# P04_McuConfig.net
KiCad netlist of a schematic drawn in Altium Designer
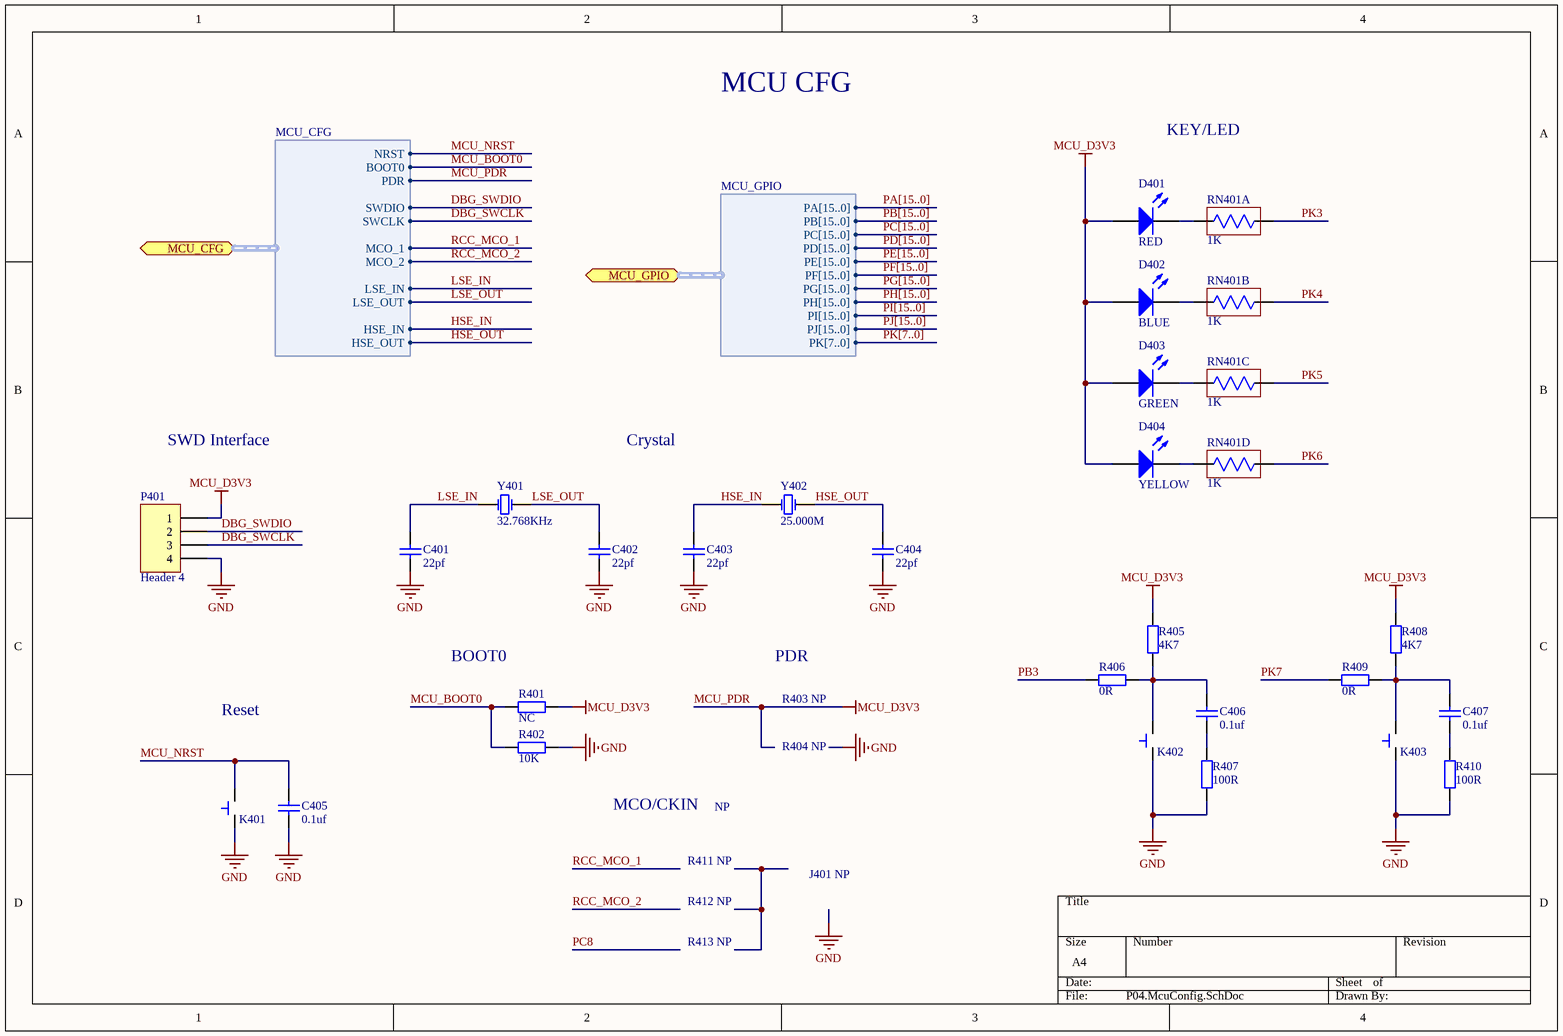
[diagram p0: P04.McuConfig.SchDoc]

(export (version "E")
  (design (tool "Eeschema 10.0.6"))
  (components
    (comp (ref "C401")
      (value "22pf")
      (footprint "C0402")
      (fields (field (name "Comment") "Cap"))
      (libsource (lib "carrot_lib") (part "Cap"))
    )
    (comp (ref "C402")
      (value "22pf")
      (footprint "C0402")
      (fields (field (name "Comment") "Cap"))
      (libsource (lib "carrot_lib") (part "Cap"))
    )
    (comp (ref "C403")
      (value "22pf")
      (footprint "C0402")
      (fields (field (name "Comment") "Cap"))
      (libsource (lib "carrot_lib") (part "Cap"))
    )
    (comp (ref "C404")
      (value "22pf")
      (footprint "C0402")
      (fields (field (name "Comment") "Cap"))
      (libsource (lib "carrot_lib") (part "Cap"))
    )
    (comp (ref "C405")
      (value "0.1uf")
      (footprint "C0603")
      (fields (field (name "Comment") "Cap"))
      (libsource (lib "carrot_lib") (part "Cap"))
    )
    (comp (ref "C406")
      (value "0.1uf")
      (footprint "C0603")
      (fields (field (name "Comment") "Cap"))
      (libsource (lib "carrot_lib") (part "Cap"))
    )
    (comp (ref "C407")
      (value "0.1uf")
      (footprint "C0603")
      (fields (field (name "Comment") "Cap"))
      (libsource (lib "carrot_lib") (part "Cap"))
    )
    (comp (ref "D401")
      (value "RED")
      (footprint "LED0603")
      (fields (field (name "Comment") "LED"))
      (libsource (lib "carrot_lib") (part "LED"))
    )
    (comp (ref "D402")
      (value "BLUE")
      (footprint "LED0603")
      (fields (field (name "Comment") "LED"))
      (libsource (lib "carrot_lib") (part "LED"))
    )
    (comp (ref "D403")
      (value "GREEN")
      (footprint "LED0603")
      (fields (field (name "Comment") "LED"))
      (libsource (lib "carrot_lib") (part "LED"))
    )
    (comp (ref "D404")
      (value "YELLOW")
      (footprint "LED0603")
      (fields (field (name "Comment") "LED"))
      (libsource (lib "carrot_lib") (part "LED"))
    )
    (comp (ref "K401")
      (value "Button")
      (footprint "Button-SMD-3.0x4.0x2.0")
      (description "微动开关")
      (libsource (lib "carrot_lib") (part "Button"))
    )
    (comp (ref "K402")
      (value "Button")
      (footprint "Button-SMD-3.0x4.0x2.0")
      (description "微动开关")
      (libsource (lib "carrot_lib") (part "Button"))
    )
    (comp (ref "K403")
      (value "Button")
      (footprint "Button-SMD-3.0x4.0x2.0")
      (description "微动开关")
      (libsource (lib "carrot_lib") (part "Button"))
    )
    (comp (ref "P401")
      (value "Header 4")
      (footprint "HDR1X4")
      (description "Header, 4-Pin")
      (fields (field (name "PUBLISHER") "Altium Limited"))
      (libsource (lib "carrot_lib") (part "Header 4"))
    )
    (comp (ref "R401")
      (value "NC")
      (footprint "R0603")
      (description "电阻")
      (fields (field (name "Comment") "Res"))
      (libsource (lib "") (part "Res_1"))
    )
    (comp (ref "R402")
      (value "10K")
      (footprint "R0603")
      (description "电阻")
      (fields (field (name "Comment") "Res"))
      (libsource (lib "") (part "Res_1"))
    )
    (comp (ref "R405")
      (value "4K7")
      (footprint "R0603")
      (description "电阻")
      (fields (field (name "Comment") "Res"))
      (libsource (lib "carrot_lib") (part "Res"))
    )
    (comp (ref "R406")
      (value "0R")
      (footprint "R0603")
      (description "电阻")
      (fields (field (name "Comment") "Res"))
      (libsource (lib "") (part "Res_1"))
    )
    (comp (ref "R407")
      (value "100R")
      (footprint "R0603")
      (description "电阻")
      (fields (field (name "Comment") "Res"))
      (libsource (lib "carrot_lib") (part "Res"))
    )
    (comp (ref "R408")
      (value "4K7")
      (footprint "R0603")
      (description "电阻")
      (fields (field (name "Comment") "Res"))
      (libsource (lib "carrot_lib") (part "Res"))
    )
    (comp (ref "R409")
      (value "0R")
      (footprint "R0603")
      (description "电阻")
      (fields (field (name "Comment") "Res"))
      (libsource (lib "") (part "Res_1"))
    )
    (comp (ref "R410")
      (value "100R")
      (footprint "R0603")
      (description "电阻")
      (fields (field (name "Comment") "Res"))
      (libsource (lib "carrot_lib") (part "Res"))
    )
    (comp (ref "RN401")
      (value "1K")
      (footprint "RA0603")
      (description "贴片排阻")
      (fields (field (name "Comment") "Res Array"))
      (libsource (lib "carrot_lib") (part "Res Array 2"))
    )
    (comp (ref "Y401")
      (value "32.768KHz")
      (footprint "XTAL-3215")
      (description "Crystal Oscillator")
      (fields (field (name "Comment") "XTAL"))
      (libsource (lib "carrot_lib") (part "XTAL"))
    )
    (comp (ref "Y402")
      (value "25.000M")
      (footprint "XTAL-3225")
      (description "Crystal Oscillator")
      (fields (field (name "Comment") "XTAL"))
      (libsource (lib "carrot_lib") (part "XTAL3"))
    )
  )
  (nets
    (net (code "148") (name "/DBG_SWCLK") (class "Default")
      (node (ref "P401") (pin "3") (pinfunction "3_3") (pintype "passive"))
    )
    (net (code "149") (name "/DBG_SWDIO") (class "Default")
      (node (ref "P401") (pin "2") (pinfunction "2_2") (pintype "passive"))
    )
    (net (code "150") (name "/HSE_IN") (class "Default")
      (node (ref "C403") (pin "2") (pinfunction "2_2") (pintype "passive"))
      (node (ref "Y402") (pin "1") (pinfunction "OSC1_1") (pintype "passive"))
    )
    (net (code "151") (name "/HSE_OUT") (class "Default")
      (node (ref "C404") (pin "2") (pinfunction "2_2") (pintype "passive"))
      (node (ref "Y402") (pin "3") (pinfunction "OSC2_3") (pintype "passive"))
    )
    (net (code "152") (name "/LSE_IN") (class "Default")
      (node (ref "C401") (pin "2") (pinfunction "2_2") (pintype "passive"))
      (node (ref "Y401") (pin "1") (pinfunction "OSC1_1") (pintype "passive"))
    )
    (net (code "153") (name "/LSE_OUT") (class "Default")
      (node (ref "C402") (pin "2") (pinfunction "2_2") (pintype "passive"))
      (node (ref "Y401") (pin "2") (pinfunction "OSC2_2") (pintype "passive"))
    )
    (net (code "154") (name "/MCU_BOOT0") (class "Default")
      (node (ref "R401") (pin "1") (pinfunction "1_1") (pintype "passive"))
      (node (ref "R402") (pin "1") (pinfunction "1_1") (pintype "passive"))
    )
    (net (code "156") (name "/MCU_NRST") (class "Default")
      (node (ref "C405") (pin "2") (pinfunction "2_2") (pintype "passive"))
      (node (ref "K401") (pin "2") (pinfunction "OUT_2") (pintype "passive"))
    )
    (net (code "157") (name "/PB3") (class "Default")
      (node (ref "R406") (pin "1") (pinfunction "1_1") (pintype "passive"))
    )
    (net (code "168") (name "/PK3") (class "Default")
      (node (ref "RN401") (pin "8") (pinfunction "8_8") (pintype "passive"))
    )
    (net (code "169") (name "/PK4") (class "Default")
      (node (ref "RN401") (pin "7") (pinfunction "7_7") (pintype "passive"))
    )
    (net (code "170") (name "/PK5") (class "Default")
      (node (ref "RN401") (pin "6") (pinfunction "6_6") (pintype "passive"))
    )
    (net (code "171") (name "/PK6") (class "Default")
      (node (ref "RN401") (pin "5") (pinfunction "5_5") (pintype "passive"))
    )
    (net (code "172") (name "/PK7") (class "Default")
      (node (ref "R409") (pin "1") (pinfunction "1_1") (pintype "passive"))
    )
    (net (code "178") (name "GND") (class "Default")
      (node (ref "C401") (pin "1") (pinfunction "1_1") (pintype "passive"))
      (node (ref "C402") (pin "1") (pinfunction "1_1") (pintype "passive"))
      (node (ref "C403") (pin "1") (pinfunction "1_1") (pintype "passive"))
      (node (ref "C404") (pin "1") (pinfunction "1_1") (pintype "passive"))
      (node (ref "C405") (pin "1") (pinfunction "1_1") (pintype "passive"))
      (node (ref "K401") (pin "1") (pinfunction "IN_1") (pintype "passive"))
      (node (ref "K402") (pin "1") (pinfunction "IN_1") (pintype "passive"))
      (node (ref "K403") (pin "1") (pinfunction "IN_1") (pintype "passive"))
      (node (ref "P401") (pin "4") (pinfunction "4_4") (pintype "passive"))
      (node (ref "R402") (pin "2") (pinfunction "2_2") (pintype "passive"))
      (node (ref "R407") (pin "1") (pinfunction "1_1") (pintype "passive"))
      (node (ref "R410") (pin "1") (pinfunction "1_1") (pintype "passive"))
    )
    (net (code "179") (name "MCU_D3V3") (class "Default")
      (node (ref "D401") (pin "1") (pinfunction "A_1") (pintype "passive"))
      (node (ref "D402") (pin "1") (pinfunction "A_1") (pintype "passive"))
      (node (ref "D403") (pin "1") (pinfunction "A_1") (pintype "passive"))
      (node (ref "D404") (pin "1") (pinfunction "A_1") (pintype "passive"))
      (node (ref "P401") (pin "1") (pinfunction "1_1") (pintype "passive"))
      (node (ref "R401") (pin "2") (pinfunction "2_2") (pintype "passive"))
      (node (ref "R405") (pin "2") (pinfunction "2_2") (pintype "passive"))
      (node (ref "R408") (pin "2") (pinfunction "2_2") (pintype "passive"))
    )
    (net (code "180") (name "Net-(C406-Pad1)") (class "Default")
      (node (ref "C406") (pin "1") (pinfunction "1_1") (pintype "passive"))
      (node (ref "R407") (pin "2") (pinfunction "2_2") (pintype "passive"))
    )
    (net (code "181") (name "Net-(C407-Pad1)") (class "Default")
      (node (ref "C407") (pin "1") (pinfunction "1_1") (pintype "passive"))
      (node (ref "R410") (pin "2") (pinfunction "2_2") (pintype "passive"))
    )
    (net (code "182") (name "Net-(D401-K)") (class "Default")
      (node (ref "D401") (pin "2") (pinfunction "K_2") (pintype "passive"))
      (node (ref "RN401") (pin "1") (pinfunction "1_1") (pintype "passive"))
    )
    (net (code "183") (name "Net-(D402-K)") (class "Default")
      (node (ref "D402") (pin "2") (pinfunction "K_2") (pintype "passive"))
      (node (ref "RN401") (pin "2") (pinfunction "2_2") (pintype "passive"))
    )
    (net (code "184") (name "Net-(D403-K)") (class "Default")
      (node (ref "D403") (pin "2") (pinfunction "K_2") (pintype "passive"))
      (node (ref "RN401") (pin "3") (pinfunction "3_3") (pintype "passive"))
    )
    (net (code "185") (name "Net-(D404-K)") (class "Default")
      (node (ref "D404") (pin "2") (pinfunction "K_2") (pintype "passive"))
      (node (ref "RN401") (pin "4") (pinfunction "4_4") (pintype "passive"))
    )
    (net (code "186") (name "Net-(K402-OUT)") (class "Default")
      (node (ref "C406") (pin "2") (pinfunction "2_2") (pintype "passive"))
      (node (ref "K402") (pin "2") (pinfunction "OUT_2") (pintype "passive"))
      (node (ref "R405") (pin "1") (pinfunction "1_1") (pintype "passive"))
      (node (ref "R406") (pin "2") (pinfunction "2_2") (pintype "passive"))
    )
    (net (code "187") (name "Net-(K403-OUT)") (class "Default")
      (node (ref "C407") (pin "2") (pinfunction "2_2") (pintype "passive"))
      (node (ref "K403") (pin "2") (pinfunction "OUT_2") (pintype "passive"))
      (node (ref "R408") (pin "1") (pinfunction "1_1") (pintype "passive"))
      (node (ref "R409") (pin "2") (pinfunction "2_2") (pintype "passive"))
    )
  )
)
